# sch.net
KiCad netlist of a schematic drawn in Altium Designer
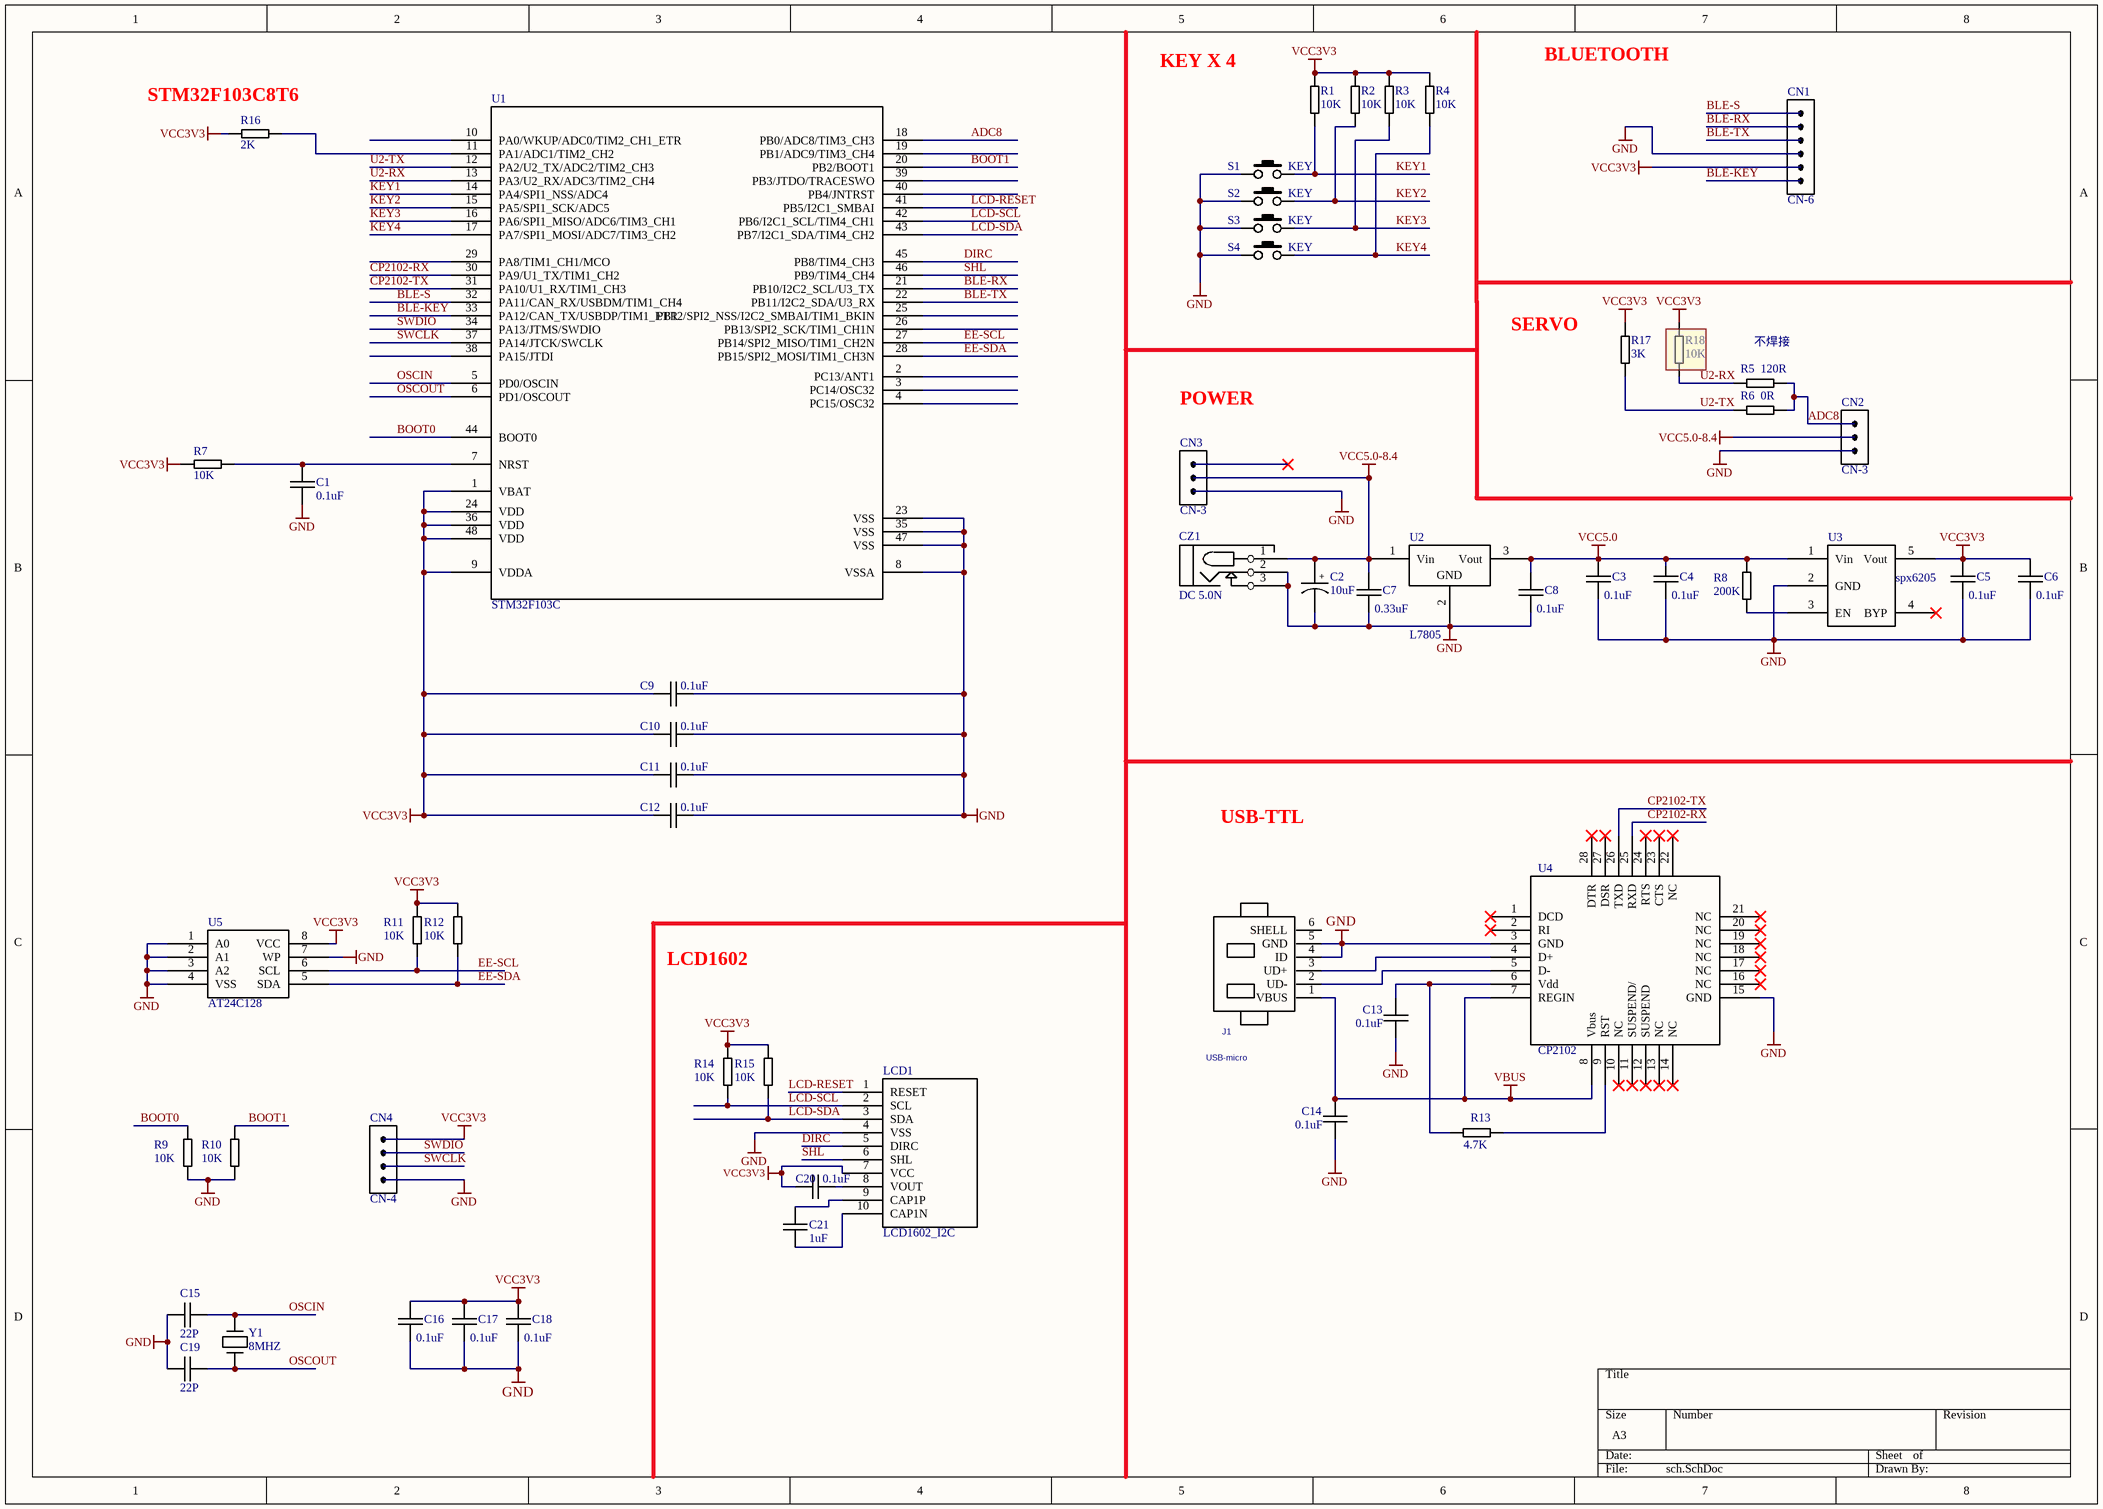
[diagram p0: sch.SchDoc]

(export (version "E")
  (design (tool "Eeschema 10.0.6"))
  (components
    (comp (ref "C1")
      (value "0.1uF")
      (footprint "CAP-0603")
      (description "Capacitor")
      (libsource (lib "综合元件") (part "CAP"))
    )
    (comp (ref "C2")
      (value "10uF")
      (footprint "CAP-A")
      (description "Polar Capacitor")
      (libsource (lib "1-Components") (part "CAP(POL)"))
    )
    (comp (ref "C3")
      (value "0.1uF")
      (footprint "CAP-0603")
      (description "Capacitor")
      (libsource (lib "综合元件") (part "CAP"))
    )
    (comp (ref "C4")
      (value "0.1uF")
      (footprint "CAP-0603")
      (description "Capacitor")
      (libsource (lib "综合元件") (part "CAP"))
    )
    (comp (ref "C5")
      (value "0.1uF")
      (footprint "CAP-0603")
      (description "Capacitor")
      (libsource (lib "综合元件") (part "CAP"))
    )
    (comp (ref "C6")
      (value "0.1uF")
      (footprint "CAP-0603")
      (description "Capacitor")
      (libsource (lib "综合元件") (part "CAP"))
    )
    (comp (ref "C7")
      (value "0.33uF")
      (footprint "CAP-0603")
      (description "Capacitor")
      (libsource (lib "综合元件") (part "CAP"))
    )
    (comp (ref "C8")
      (value "0.1uF")
      (footprint "CAP-0603")
      (description "Capacitor")
      (libsource (lib "综合元件") (part "CAP"))
    )
    (comp (ref "C9")
      (value "0.1uF")
      (footprint "CAP-0603")
      (description "Capacitor")
      (libsource (lib "综合元件") (part "CAP"))
    )
    (comp (ref "C10")
      (value "0.1uF")
      (footprint "CAP-0603")
      (description "Capacitor")
      (libsource (lib "综合元件") (part "CAP"))
    )
    (comp (ref "C11")
      (value "0.1uF")
      (footprint "CAP-0603")
      (description "Capacitor")
      (libsource (lib "综合元件") (part "CAP"))
    )
    (comp (ref "C12")
      (value "0.1uF")
      (footprint "CAP-0603")
      (description "Capacitor")
      (libsource (lib "综合元件") (part "CAP"))
    )
    (comp (ref "C13")
      (value "0.1uF")
      (footprint "CAP-0603")
      (description "Capacitor")
      (libsource (lib "综合元件") (part "CAP"))
    )
    (comp (ref "C14")
      (value "0.1uF")
      (footprint "CAP-0603")
      (description "Capacitor")
      (libsource (lib "综合元件") (part "CAP"))
    )
    (comp (ref "C15")
      (value "22P")
      (footprint "CAP-0603")
      (description "Capacitor")
      (libsource (lib "1-Components") (part "CAP"))
    )
    (comp (ref "C16")
      (value "0.1uF")
      (footprint "CAP-0603")
      (description "Capacitor")
      (libsource (lib "综合元件") (part "CAP"))
    )
    (comp (ref "C17")
      (value "0.1uF")
      (footprint "CAP-0603")
      (description "Capacitor")
      (libsource (lib "综合元件") (part "CAP"))
    )
    (comp (ref "C18")
      (value "0.1uF")
      (footprint "CAP-0603")
      (description "Capacitor")
      (libsource (lib "综合元件") (part "CAP"))
    )
    (comp (ref "C19")
      (value "22P")
      (footprint "CAP-0603")
      (description "Capacitor")
      (libsource (lib "1-Components") (part "CAP"))
    )
    (comp (ref "C20")
      (value "0.1uF")
      (footprint "CAP-0603")
      (description "Capacitor")
      (libsource (lib "综合元件") (part "CAP"))
    )
    (comp (ref "C21")
      (value "1uF")
      (footprint "CAP-0603")
      (description "Capacitor")
      (libsource (lib "综合元件") (part "CAP"))
    )
    (comp (ref "CN1") (value "CN-6") (footprint "CN-6") (libsource (lib "2-Connectors") (part "CN-6")))
    (comp (ref "CN2") (value "CN-3") (footprint "IDC-3×1") (libsource (lib "2-Connectors") (part "CN-3")))
    (comp (ref "CN3") (value "CN-3") (footprint "IDC-3×1") (libsource (lib "2-Connectors") (part "CN-3")))
    (comp (ref "CN4") (value "CN-4") (footprint "IDC-4×1") (libsource (lib "2-Connectors") (part "CN-4")))
    (comp (ref "CZ1")
      (value "DC 5.0N")
      (footprint "DC-005(N)")
      (libsource (lib "2-Connectors") (part "DC 5.0N"))
    )
    (comp (ref "J1")
      (value "USB-micro")
      (footprint "USB-MICRO")
      (libsource (lib "2-Connectors") (part "USB-micro"))
    )
    (comp (ref "LCD1")
      (value "LCD1602_I2C")
      (footprint "LCD-IIC")
      (description "LCD1602")
      (libsource (lib "6-Modulars") (part "LCD1602_I2C"))
    )
    (comp (ref "R1")
      (value "10K")
      (footprint "RES-0603")
      (description "Resistor")
      (libsource (lib "1-Components") (part "RES"))
    )
    (comp (ref "R2")
      (value "10K")
      (footprint "RES-0603")
      (description "Resistor")
      (libsource (lib "1-Components") (part "RES"))
    )
    (comp (ref "R3")
      (value "10K")
      (footprint "RES-0603")
      (description "Resistor")
      (libsource (lib "1-Components") (part "RES"))
    )
    (comp (ref "R4")
      (value "10K")
      (footprint "RES-0603")
      (description "Resistor")
      (libsource (lib "1-Components") (part "RES"))
    )
    (comp (ref "R5")
      (value "120R")
      (footprint "RES-0603")
      (description "Resistor")
      (libsource (lib "1-Components") (part "RES"))
    )
    (comp (ref "R6")
      (value "0R")
      (footprint "RES-0603")
      (description "Resistor")
      (libsource (lib "1-Components") (part "RES"))
    )
    (comp (ref "R7")
      (value "10K")
      (footprint "RES-0603")
      (description "Resistor")
      (libsource (lib "综合元件") (part "RES"))
    )
    (comp (ref "R8")
      (value "200K")
      (footprint "RES-0603")
      (description "Resistor")
      (libsource (lib "1-Components") (part "RES"))
    )
    (comp (ref "R9")
      (value "10K")
      (footprint "RES-0603")
      (description "Resistor")
      (libsource (lib "1-Components") (part "RES"))
    )
    (comp (ref "R10")
      (value "10K")
      (footprint "RES-0603")
      (description "Resistor")
      (libsource (lib "1-Components") (part "RES"))
    )
    (comp (ref "R11")
      (value "10K")
      (footprint "RES-0603")
      (description "Resistor")
      (libsource (lib "1-Components") (part "RES"))
    )
    (comp (ref "R12")
      (value "10K")
      (footprint "RES-0603")
      (description "Resistor")
      (libsource (lib "1-Components") (part "RES"))
    )
    (comp (ref "R13")
      (value "4.7K")
      (footprint "RES-0603")
      (description "Resistor")
      (libsource (lib "1-Components") (part "RES"))
    )
    (comp (ref "R14")
      (value "10K")
      (footprint "RES-0603")
      (description "Resistor")
      (libsource (lib "1-Components") (part "RES"))
    )
    (comp (ref "R15")
      (value "10K")
      (footprint "RES-0603")
      (description "Resistor")
      (libsource (lib "1-Components") (part "RES"))
    )
    (comp (ref "R16")
      (value "2K")
      (footprint "RES-0603")
      (description "Resistor")
      (libsource (lib "1-Components") (part "RES"))
    )
    (comp (ref "R17")
      (value "3K")
      (footprint "RES-0603")
      (description "Resistor")
      (libsource (lib "1-Components") (part "RES"))
    )
    (comp (ref "R18")
      (value "10K")
      (footprint "RES-0603")
      (description "Resistor")
      (libsource (lib "1-Components") (part "RES"))
    )
    (comp (ref "S1") (value "KEY") (footprint "KEY-4X4X1.5") (libsource (lib "2-Connectors") (part "KEY")))
    (comp (ref "S2") (value "KEY") (footprint "KEY-4X4X1.5") (libsource (lib "2-Connectors") (part "KEY")))
    (comp (ref "S3") (value "KEY") (footprint "KEY-4X4X1.5") (libsource (lib "2-Connectors") (part "KEY")))
    (comp (ref "S4") (value "KEY") (footprint "KEY-4X4X1.5") (libsource (lib "2-Connectors") (part "KEY")))
    (comp (ref "U1")
      (value "STM32F103C")
      (footprint "LQFP-48")
      (fields (field (name "PUBLISHER") "Altium Limited"))
      (libsource (lib "5-ICs Mcu") (part "STM32F103C(LQFP)"))
    )
    (comp (ref "U2") (value "L7805") (footprint "TO-252") (libsource (lib "3-ICs Normal") (part "78XX")))
    (comp (ref "U3")
      (value "spx6205")
      (footprint "SOT-23(5)")
      (libsource (lib "3-ICs Normal") (part "SP6205(FIXED)"))
    )
    (comp (ref "U4") (value "CP2102") (footprint "QFN-28") (libsource (lib "5-ICs Mcu") (part "MPU6050_1")))
    (comp (ref "U5")
      (value "AT24C128")
      (footprint "SOP-8(3.9)")
      (libsource (lib "3-ICs Normal") (part "AT24C128"))
    )
    (comp (ref "Y1")
      (value "8MHZ")
      (footprint "XTAL-2512")
      (description "Crystal")
      (libsource (lib "1-Components") (part "XTAL(1)"))
    )
  )
  (nets
    (net (code "1") (name "/ADC8") (class "Default")
      (node (ref "CN2") (pin "1") (pinfunction "1_1") (pintype "passive"))
      (node (ref "R5") (pin "2") (pinfunction "2_2") (pintype "passive"))
      (node (ref "R6") (pin "2") (pinfunction "2_2") (pintype "passive"))
      (node (ref "U1") (pin "18") (pinfunction "PB0/ADC8/TIM3_CH3_18") (pintype "passive"))
    )
    (net (code "2") (name "/BLE-KEY") (class "Default")
      (node (ref "CN1") (pin "6") (pinfunction "6_6") (pintype "passive"))
      (node (ref "U1") (pin "33") (pinfunction "PA12/CAN_TX/USBDP/TIM1_ETR_33") (pintype "passive"))
    )
    (net (code "3") (name "/BLE-RX") (class "Default")
      (node (ref "CN1") (pin "2") (pinfunction "2_2") (pintype "passive"))
      (node (ref "U1") (pin "21") (pinfunction "PB10/I2C2_SCL/U3_TX_21") (pintype "passive"))
    )
    (net (code "4") (name "/BLE-S") (class "Default")
      (node (ref "CN1") (pin "1") (pinfunction "1_1") (pintype "passive"))
      (node (ref "U1") (pin "32") (pinfunction "PA11/CAN_RX/USBDM/TIM1_CH4_32") (pintype "passive"))
    )
    (net (code "5") (name "/BLE-TX") (class "Default")
      (node (ref "CN1") (pin "3") (pinfunction "3_3") (pintype "passive"))
      (node (ref "U1") (pin "22") (pinfunction "PB11/I2C2_SDA/U3_RX_22") (pintype "passive"))
    )
    (net (code "6") (name "/BOOT0") (class "Default")
      (node (ref "R9") (pin "1") (pinfunction "1_1") (pintype "passive"))
      (node (ref "U1") (pin "44") (pinfunction "BOOT0_44") (pintype "passive"))
    )
    (net (code "7") (name "/BOOT1") (class "Default")
      (node (ref "R10") (pin "1") (pinfunction "1_1") (pintype "passive"))
      (node (ref "U1") (pin "20") (pinfunction "PB2/BOOT1_20") (pintype "passive"))
    )
    (net (code "8") (name "/CP2102-RX") (class "Default")
      (node (ref "U1") (pin "30") (pinfunction "PA9/U1_TX/TIM1_CH2_30") (pintype "passive"))
      (node (ref "U4") (pin "25") (pinfunction "RXD_25") (pintype "passive"))
    )
    (net (code "9") (name "/CP2102-TX") (class "Default")
      (node (ref "U1") (pin "31") (pinfunction "PA10/U1_RX/TIM1_CH3_31") (pintype "passive"))
      (node (ref "U4") (pin "26") (pinfunction "TXD_26") (pintype "passive"))
    )
    (net (code "10") (name "/DIRC") (class "Default")
      (node (ref "LCD1") (pin "5") (pinfunction "DIRC_5") (pintype "passive"))
      (node (ref "U1") (pin "45") (pinfunction "PB8/TIM4_CH3_45") (pintype "passive"))
    )
    (net (code "11") (name "/EE-SCL") (class "Default")
      (node (ref "R11") (pin "2") (pinfunction "2_2") (pintype "passive"))
      (node (ref "U1") (pin "27") (pinfunction "PB14/SPI2_MISO/TIM1_CH2N_27") (pintype "passive"))
      (node (ref "U5") (pin "6") (pinfunction "SCL_6") (pintype "passive"))
    )
    (net (code "12") (name "/EE-SDA") (class "Default")
      (node (ref "R12") (pin "2") (pinfunction "2_2") (pintype "passive"))
      (node (ref "U1") (pin "28") (pinfunction "PB15/SPI2_MOSI/TIM1_CH3N_28") (pintype "passive"))
      (node (ref "U5") (pin "5") (pinfunction "SDA_5") (pintype "passive"))
    )
    (net (code "13") (name "/KEY1") (class "Default")
      (node (ref "R1") (pin "1") (pinfunction "1_1") (pintype "passive"))
      (node (ref "S1") (pin "2") (pinfunction "2_2") (pintype "passive"))
      (node (ref "U1") (pin "14") (pinfunction "PA4/SPI1_NSS/ADC4_14") (pintype "passive"))
    )
    (net (code "14") (name "/KEY2") (class "Default")
      (node (ref "R2") (pin "1") (pinfunction "1_1") (pintype "passive"))
      (node (ref "S2") (pin "2") (pinfunction "2_2") (pintype "passive"))
      (node (ref "U1") (pin "15") (pinfunction "PA5/SPI1_SCK/ADC5_15") (pintype "passive"))
    )
    (net (code "15") (name "/KEY3") (class "Default")
      (node (ref "R3") (pin "1") (pinfunction "1_1") (pintype "passive"))
      (node (ref "S3") (pin "2") (pinfunction "2_2") (pintype "passive"))
      (node (ref "U1") (pin "16") (pinfunction "PA6/SPI1_MISO/ADC6/TIM3_CH1_16") (pintype "passive"))
    )
    (net (code "16") (name "/KEY4") (class "Default")
      (node (ref "R4") (pin "1") (pinfunction "1_1") (pintype "passive"))
      (node (ref "S4") (pin "2") (pinfunction "2_2") (pintype "passive"))
      (node (ref "U1") (pin "17") (pinfunction "PA7/SPI1_MOSI/ADC7/TIM3_CH2_17") (pintype "passive"))
    )
    (net (code "17") (name "/LCD-RESET") (class "Default")
      (node (ref "LCD1") (pin "1") (pinfunction "RESET_1") (pintype "passive"))
      (node (ref "U1") (pin "41") (pinfunction "PB5/I2C1_SMBAI_41") (pintype "passive"))
    )
    (net (code "18") (name "/LCD-SCL") (class "Default")
      (node (ref "LCD1") (pin "2") (pinfunction "SCL_2") (pintype "passive"))
      (node (ref "R14") (pin "2") (pinfunction "2_2") (pintype "passive"))
      (node (ref "U1") (pin "42") (pinfunction "PB6/I2C1_SCL/TIM4_CH1_42") (pintype "passive"))
    )
    (net (code "19") (name "/LCD-SDA") (class "Default")
      (node (ref "LCD1") (pin "3") (pinfunction "SDA_3") (pintype "passive"))
      (node (ref "R15") (pin "2") (pinfunction "2_2") (pintype "passive"))
      (node (ref "U1") (pin "43") (pinfunction "PB7/I2C1_SDA/TIM4_CH2_43") (pintype "passive"))
    )
    (net (code "20") (name "/OSCIN") (class "Default")
      (node (ref "C15") (pin "2") (pinfunction "2_2") (pintype "passive"))
      (node (ref "U1") (pin "5") (pinfunction "PD0/OSCIN_5") (pintype "passive"))
      (node (ref "Y1") (pin "2") (pinfunction "2_2") (pintype "passive"))
    )
    (net (code "21") (name "/OSCOUT") (class "Default")
      (node (ref "C19") (pin "2") (pinfunction "2_2") (pintype "passive"))
      (node (ref "U1") (pin "6") (pinfunction "PD1/OSCOUT_6") (pintype "passive"))
      (node (ref "Y1") (pin "1") (pinfunction "1_1") (pintype "passive"))
    )
    (net (code "22") (name "/SHL") (class "Default")
      (node (ref "LCD1") (pin "6") (pinfunction "SHL_6") (pintype "passive"))
      (node (ref "U1") (pin "46") (pinfunction "PB9/TIM4_CH4_46") (pintype "passive"))
    )
    (net (code "23") (name "/SWCLK") (class "Default")
      (node (ref "CN4") (pin "3") (pinfunction "3_3") (pintype "passive"))
      (node (ref "U1") (pin "37") (pinfunction "PA14/JTCK/SWCLK_37") (pintype "passive"))
    )
    (net (code "24") (name "/SWDIO") (class "Default")
      (node (ref "CN4") (pin "2") (pinfunction "2_2") (pintype "passive"))
      (node (ref "U1") (pin "34") (pinfunction "PA13/JTMS/SWDIO_34") (pintype "passive"))
    )
    (net (code "25") (name "/U2-RX") (class "Default")
      (node (ref "R18") (pin "1") (pinfunction "1_1") (pintype "passive"))
      (node (ref "R5") (pin "1") (pinfunction "1_1") (pintype "passive"))
      (node (ref "U1") (pin "13") (pinfunction "PA3/U2_RX/ADC3/TIM2_CH4_13") (pintype "passive"))
    )
    (net (code "26") (name "/U2-TX") (class "Default")
      (node (ref "R17") (pin "1") (pinfunction "1_1") (pintype "passive"))
      (node (ref "R6") (pin "1") (pinfunction "1_1") (pintype "passive"))
      (node (ref "U1") (pin "12") (pinfunction "PA2/U2_TX/ADC2/TIM2_CH3_12") (pintype "passive"))
    )
    (net (code "27") (name "GND") (class "Default")
      (node (ref "C1") (pin "2") (pinfunction "2_2") (pintype "passive"))
      (node (ref "C10") (pin "1") (pinfunction "1_1") (pintype "passive"))
      (node (ref "C11") (pin "1") (pinfunction "1_1") (pintype "passive"))
      (node (ref "C12") (pin "1") (pinfunction "1_1") (pintype "passive"))
      (node (ref "C13") (pin "2") (pinfunction "2_2") (pintype "passive"))
      (node (ref "C14") (pin "2") (pinfunction "2_2") (pintype "passive"))
      (node (ref "C15") (pin "1") (pinfunction "1_1") (pintype "passive"))
      (node (ref "C16") (pin "2") (pinfunction "2_2") (pintype "passive"))
      (node (ref "C17") (pin "2") (pinfunction "2_2") (pintype "passive"))
      (node (ref "C18") (pin "2") (pinfunction "2_2") (pintype "passive"))
      (node (ref "C19") (pin "1") (pinfunction "1_1") (pintype "passive"))
      (node (ref "C2") (pin "2") (pinfunction "2_2") (pintype "passive"))
      (node (ref "C3") (pin "2") (pinfunction "2_2") (pintype "passive"))
      (node (ref "C4") (pin "2") (pinfunction "2_2") (pintype "passive"))
      (node (ref "C5") (pin "2") (pinfunction "2_2") (pintype "passive"))
      (node (ref "C6") (pin "2") (pinfunction "2_2") (pintype "passive"))
      (node (ref "C7") (pin "2") (pinfunction "2_2") (pintype "passive"))
      (node (ref "C8") (pin "2") (pinfunction "2_2") (pintype "passive"))
      (node (ref "C9") (pin "1") (pinfunction "1_1") (pintype "passive"))
      (node (ref "CN1") (pin "4") (pinfunction "4_4") (pintype "passive"))
      (node (ref "CN2") (pin "3") (pinfunction "3_3") (pintype "passive"))
      (node (ref "CN3") (pin "3") (pinfunction "3_3") (pintype "passive"))
      (node (ref "CN4") (pin "4") (pinfunction "4_4") (pintype "passive"))
      (node (ref "CZ1") (pin "2") (pinfunction "A_2") (pintype "passive"))
      (node (ref "CZ1") (pin "3") (pinfunction "B_3") (pintype "passive"))
      (node (ref "J1") (pin "4") (pinfunction "ID_4") (pintype "passive"))
      (node (ref "J1") (pin "5") (pinfunction "GND_5") (pintype "passive"))
      (node (ref "LCD1") (pin "4") (pinfunction "VSS_4") (pintype "passive"))
      (node (ref "R10") (pin "2") (pinfunction "2_2") (pintype "passive"))
      (node (ref "R9") (pin "2") (pinfunction "2_2") (pintype "passive"))
      (node (ref "S1") (pin "1") (pinfunction "1_1") (pintype "passive"))
      (node (ref "S2") (pin "1") (pinfunction "1_1") (pintype "passive"))
      (node (ref "S3") (pin "1") (pinfunction "1_1") (pintype "passive"))
      (node (ref "S4") (pin "1") (pinfunction "1_1") (pintype "passive"))
      (node (ref "U1") (pin "23") (pinfunction "VSS_23") (pintype "passive"))
      (node (ref "U1") (pin "35") (pinfunction "VSS_35") (pintype "passive"))
      (node (ref "U1") (pin "47") (pinfunction "VSS_47") (pintype "passive"))
      (node (ref "U1") (pin "8") (pinfunction "VSSA_8") (pintype "passive"))
      (node (ref "U2") (pin "2") (pinfunction "GND_2") (pintype "passive"))
      (node (ref "U3") (pin "2") (pinfunction "GND_2") (pintype "passive"))
      (node (ref "U4") (pin "15") (pinfunction "GND_15") (pintype "passive"))
      (node (ref "U4") (pin "3") (pinfunction "GND_3") (pintype "passive"))
      (node (ref "U5") (pin "1") (pinfunction "A0_1") (pintype "passive"))
      (node (ref "U5") (pin "2") (pinfunction "A1_2") (pintype "passive"))
      (node (ref "U5") (pin "3") (pinfunction "A2_3") (pintype "passive"))
      (node (ref "U5") (pin "4") (pinfunction "VSS_4") (pintype "passive"))
      (node (ref "U5") (pin "7") (pinfunction "WP_7") (pintype "passive"))
    )
    (net (code "28") (name "Net-(J1-UD+)") (class "Default")
      (node (ref "J1") (pin "3") (pinfunction "UD+_3") (pintype "passive"))
      (node (ref "U4") (pin "4") (pinfunction "D+_4") (pintype "passive"))
    )
    (net (code "29") (name "Net-(J1-UD-)") (class "Default")
      (node (ref "J1") (pin "2") (pinfunction "UD-_2") (pintype "passive"))
      (node (ref "U4") (pin "5") (pinfunction "D-_5") (pintype "passive"))
    )
    (net (code "30") (name "Net-(LCD1-CAP1N)") (class "Default")
      (node (ref "C21") (pin "2") (pinfunction "2_2") (pintype "passive"))
      (node (ref "LCD1") (pin "10") (pinfunction "CAP1N_10") (pintype "passive"))
    )
    (net (code "31") (name "Net-(LCD1-CAP1P)") (class "Default")
      (node (ref "C21") (pin "1") (pinfunction "1_1") (pintype "passive"))
      (node (ref "LCD1") (pin "9") (pinfunction "CAP1P_9") (pintype "passive"))
    )
    (net (code "32") (name "Net-(LCD1-VOUT)") (class "Default")
      (node (ref "C20") (pin "2") (pinfunction "2_2") (pintype "passive"))
      (node (ref "LCD1") (pin "8") (pinfunction "VOUT_8") (pintype "passive"))
    )
    (net (code "33") (name "Net-(U1-NRST)") (class "Default")
      (node (ref "C1") (pin "1") (pinfunction "1_1") (pintype "passive"))
      (node (ref "R7") (pin "2") (pinfunction "2_2") (pintype "passive"))
      (node (ref "U1") (pin "7") (pinfunction "NRST_7") (pintype "passive"))
    )
    (net (code "34") (name "Net-(U1-PA1{slash}ADC1{slash}TIM2_CH2)") (class "Default")
      (node (ref "R16") (pin "1") (pinfunction "1_1") (pintype "passive"))
      (node (ref "U1") (pin "11") (pinfunction "PA1/ADC1/TIM2_CH2_11") (pintype "passive"))
    )
    (net (code "35") (name "Net-(U3-EN)") (class "Default")
      (node (ref "R8") (pin "2") (pinfunction "2_2") (pintype "passive"))
      (node (ref "U3") (pin "3") (pinfunction "EN_3") (pintype "passive"))
    )
    (net (code "36") (name "Net-(U4-RST)") (class "Default")
      (node (ref "R13") (pin "2") (pinfunction "2_2") (pintype "passive"))
      (node (ref "U4") (pin "9") (pinfunction "RST_9") (pintype "passive"))
    )
    (net (code "37") (name "Net-(U4-Vdd)") (class "Default")
      (node (ref "C13") (pin "1") (pinfunction "1_1") (pintype "passive"))
      (node (ref "R13") (pin "1") (pinfunction "1_1") (pintype "passive"))
      (node (ref "U4") (pin "6") (pinfunction "Vdd_6") (pintype "passive"))
    )
    (net (code "38") (name "VBUS") (class "Default")
      (node (ref "C14") (pin "1") (pinfunction "1_1") (pintype "passive"))
      (node (ref "J1") (pin "1") (pinfunction "VBUS_1") (pintype "passive"))
      (node (ref "U4") (pin "7") (pinfunction "REGIN_7") (pintype "passive"))
      (node (ref "U4") (pin "8") (pinfunction "Vbus_8") (pintype "passive"))
    )
    (net (code "39") (name "VCC3V3") (class "Default")
      (node (ref "C10") (pin "2") (pinfunction "2_2") (pintype "passive"))
      (node (ref "C11") (pin "2") (pinfunction "2_2") (pintype "passive"))
      (node (ref "C12") (pin "2") (pinfunction "2_2") (pintype "passive"))
      (node (ref "C16") (pin "1") (pinfunction "1_1") (pintype "passive"))
      (node (ref "C17") (pin "1") (pinfunction "1_1") (pintype "passive"))
      (node (ref "C18") (pin "1") (pinfunction "1_1") (pintype "passive"))
      (node (ref "C20") (pin "1") (pinfunction "1_1") (pintype "passive"))
      (node (ref "C5") (pin "1") (pinfunction "1_1") (pintype "passive"))
      (node (ref "C6") (pin "1") (pinfunction "1_1") (pintype "passive"))
      (node (ref "C9") (pin "2") (pinfunction "2_2") (pintype "passive"))
      (node (ref "CN1") (pin "5") (pinfunction "5_5") (pintype "passive"))
      (node (ref "CN4") (pin "1") (pinfunction "1_1") (pintype "passive"))
      (node (ref "LCD1") (pin "7") (pinfunction "VCC_7") (pintype "passive"))
      (node (ref "R1") (pin "2") (pinfunction "2_2") (pintype "passive"))
      (node (ref "R11") (pin "1") (pinfunction "1_1") (pintype "passive"))
      (node (ref "R12") (pin "1") (pinfunction "1_1") (pintype "passive"))
      (node (ref "R14") (pin "1") (pinfunction "1_1") (pintype "passive"))
      (node (ref "R15") (pin "1") (pinfunction "1_1") (pintype "passive"))
      (node (ref "R16") (pin "2") (pinfunction "2_2") (pintype "passive"))
      (node (ref "R17") (pin "2") (pinfunction "2_2") (pintype "passive"))
      (node (ref "R18") (pin "2") (pinfunction "2_2") (pintype "passive"))
      (node (ref "R2") (pin "2") (pinfunction "2_2") (pintype "passive"))
      (node (ref "R3") (pin "2") (pinfunction "2_2") (pintype "passive"))
      (node (ref "R4") (pin "2") (pinfunction "2_2") (pintype "passive"))
      (node (ref "R7") (pin "1") (pinfunction "1_1") (pintype "passive"))
      (node (ref "U1") (pin "1") (pinfunction "VBAT_1") (pintype "passive"))
      (node (ref "U1") (pin "24") (pinfunction "VDD_24") (pintype "passive"))
      (node (ref "U1") (pin "36") (pinfunction "VDD_36") (pintype "passive"))
      (node (ref "U1") (pin "48") (pinfunction "VDD_48") (pintype "passive"))
      (node (ref "U1") (pin "9") (pinfunction "VDDA_9") (pintype "passive"))
      (node (ref "U3") (pin "5") (pinfunction "Vout_5") (pintype "passive"))
      (node (ref "U5") (pin "8") (pinfunction "VCC_8") (pintype "passive"))
    )
    (net (code "40") (name "VCC5.0") (class "Default")
      (node (ref "C3") (pin "1") (pinfunction "1_1") (pintype "passive"))
      (node (ref "C4") (pin "1") (pinfunction "1_1") (pintype "passive"))
      (node (ref "C8") (pin "1") (pinfunction "1_1") (pintype "passive"))
      (node (ref "R8") (pin "1") (pinfunction "1_1") (pintype "passive"))
      (node (ref "U2") (pin "3") (pinfunction "Vout_3") (pintype "passive"))
      (node (ref "U3") (pin "1") (pinfunction "Vin_1") (pintype "passive"))
    )
    (net (code "41") (name "VCC5.0-8.4") (class "Default")
      (node (ref "C2") (pin "1") (pinfunction "1_1") (pintype "passive"))
      (node (ref "C7") (pin "1") (pinfunction "1_1") (pintype "passive"))
      (node (ref "CN2") (pin "2") (pinfunction "2_2") (pintype "passive"))
      (node (ref "CN3") (pin "2") (pinfunction "2_2") (pintype "passive"))
      (node (ref "CZ1") (pin "1") (pinfunction "+_1") (pintype "passive"))
      (node (ref "U2") (pin "1") (pinfunction "Vin_1") (pintype "passive"))
    )
    (net (code "42") (name "unconnected-(CN3-Pad1)") (class "Default")
      (node (ref "CN3") (pin "1") (pinfunction "1_1") (pintype "passive+no_connect"))
    )
    (net (code "43") (name "unconnected-(J1-SHELL-Pad6)") (class "Default")
      (node (ref "J1") (pin "6") (pinfunction "SHELL_6") (pintype "passive"))
    )
    (net (code "44") (name "unconnected-(U1-PA0{slash}WKUP{slash}ADC0{slash}TIM2_CH1_ETR-Pad10)") (class "Default")
      (node (ref "U1") (pin "10") (pinfunction "PA0/WKUP/ADC0/TIM2_CH1_ETR_10") (pintype "passive"))
    )
    (net (code "45") (name "unconnected-(U1-PA8{slash}TIM1_CH1{slash}MCO-Pad29)") (class "Default")
      (node (ref "U1") (pin "29") (pinfunction "PA8/TIM1_CH1/MCO_29") (pintype "passive"))
    )
    (net (code "46") (name "unconnected-(U1-PA15{slash}JTDI-Pad38)") (class "Default")
      (node (ref "U1") (pin "38") (pinfunction "PA15/JTDI_38") (pintype "passive"))
    )
    (net (code "47") (name "unconnected-(U1-PB1{slash}ADC9{slash}TIM3_CH4-Pad19)") (class "Default")
      (node (ref "U1") (pin "19") (pinfunction "PB1/ADC9/TIM3_CH4_19") (pintype "passive"))
    )
    (net (code "48") (name "unconnected-(U1-PB3{slash}JTDO{slash}TRACESWO-Pad39)") (class "Default")
      (node (ref "U1") (pin "39") (pinfunction "PB3/JTDO/TRACESWO_39") (pintype "passive"))
    )
    (net (code "49") (name "unconnected-(U1-PB4{slash}JNTRST-Pad40)") (class "Default")
      (node (ref "U1") (pin "40") (pinfunction "PB4/JNTRST_40") (pintype "passive"))
    )
    (net (code "50") (name "unconnected-(U1-PB12{slash}SPI2_NSS{slash}I2C2_SMBAI{slash}TIM1_BKIN-Pad25)") (class "Default")
      (node (ref "U1") (pin "25") (pinfunction "PB12/SPI2_NSS/I2C2_SMBAI/TIM1_BKIN_25") (pintype "passive"))
    )
    (net (code "51") (name "unconnected-(U1-PB13{slash}SPI2_SCK{slash}TIM1_CH1N-Pad26)") (class "Default")
      (node (ref "U1") (pin "26") (pinfunction "PB13/SPI2_SCK/TIM1_CH1N_26") (pintype "passive"))
    )
    (net (code "52") (name "unconnected-(U1-PC13{slash}ANT1-Pad2)") (class "Default")
      (node (ref "U1") (pin "2") (pinfunction "PC13/ANT1_2") (pintype "passive"))
    )
    (net (code "53") (name "unconnected-(U1-PC14{slash}OSC32-Pad3)") (class "Default")
      (node (ref "U1") (pin "3") (pinfunction "PC14/OSC32_3") (pintype "passive"))
    )
    (net (code "54") (name "unconnected-(U1-PC15{slash}OSC32-Pad4)") (class "Default")
      (node (ref "U1") (pin "4") (pinfunction "PC15/OSC32_4") (pintype "passive"))
    )
    (net (code "55") (name "unconnected-(U3-BYP-Pad4)") (class "Default")
      (node (ref "U3") (pin "4") (pinfunction "BYP_4") (pintype "passive+no_connect"))
    )
    (net (code "56") (name "unconnected-(U4-CTS-Pad23)") (class "Default")
      (node (ref "U4") (pin "23") (pinfunction "CTS_23") (pintype "passive+no_connect"))
    )
    (net (code "57") (name "unconnected-(U4-DCD-Pad1)") (class "Default")
      (node (ref "U4") (pin "1") (pinfunction "DCD_1") (pintype "passive+no_connect"))
    )
    (net (code "58") (name "unconnected-(U4-DSR-Pad27)") (class "Default")
      (node (ref "U4") (pin "27") (pinfunction "DSR_27") (pintype "passive+no_connect"))
    )
    (net (code "59") (name "unconnected-(U4-DTR-Pad28)") (class "Default")
      (node (ref "U4") (pin "28") (pinfunction "DTR_28") (pintype "passive+no_connect"))
    )
    (net (code "60") (name "unconnected-(U4-NC-Pad10)") (class "Default")
      (node (ref "U4") (pin "10") (pinfunction "NC_10") (pintype "passive+no_connect"))
    )
    (net (code "61") (name "unconnected-(U4-NC-Pad13)") (class "Default")
      (node (ref "U4") (pin "13") (pinfunction "NC_13") (pintype "passive+no_connect"))
    )
    (net (code "62") (name "unconnected-(U4-NC-Pad14)") (class "Default")
      (node (ref "U4") (pin "14") (pinfunction "NC_14") (pintype "passive+no_connect"))
    )
    (net (code "63") (name "unconnected-(U4-NC-Pad16)") (class "Default")
      (node (ref "U4") (pin "16") (pinfunction "NC_16") (pintype "passive+no_connect"))
    )
    (net (code "64") (name "unconnected-(U4-NC-Pad17)") (class "Default")
      (node (ref "U4") (pin "17") (pinfunction "NC_17") (pintype "passive+no_connect"))
    )
    (net (code "65") (name "unconnected-(U4-NC-Pad18)") (class "Default")
      (node (ref "U4") (pin "18") (pinfunction "NC_18") (pintype "passive+no_connect"))
    )
    (net (code "66") (name "unconnected-(U4-NC-Pad19)") (class "Default")
      (node (ref "U4") (pin "19") (pinfunction "NC_19") (pintype "passive+no_connect"))
    )
    (net (code "67") (name "unconnected-(U4-NC-Pad20)") (class "Default")
      (node (ref "U4") (pin "20") (pinfunction "NC_20") (pintype "passive+no_connect"))
    )
    (net (code "68") (name "unconnected-(U4-NC-Pad21)") (class "Default")
      (node (ref "U4") (pin "21") (pinfunction "NC_21") (pintype "passive+no_connect"))
    )
    (net (code "69") (name "unconnected-(U4-NC-Pad22)") (class "Default")
      (node (ref "U4") (pin "22") (pinfunction "NC_22") (pintype "passive+no_connect"))
    )
    (net (code "70") (name "unconnected-(U4-RI-Pad2)") (class "Default")
      (node (ref "U4") (pin "2") (pinfunction "RI_2") (pintype "passive+no_connect"))
    )
    (net (code "71") (name "unconnected-(U4-RTS-Pad24)") (class "Default")
      (node (ref "U4") (pin "24") (pinfunction "RTS_24") (pintype "passive+no_connect"))
    )
    (net (code "72") (name "unconnected-(U4-SUSPEND-Pad12)") (class "Default")
      (node (ref "U4") (pin "12") (pinfunction "SUSPEND_12") (pintype "passive+no_connect"))
    )
    (net (code "73") (name "unconnected-(U4-SUSPEND{slash}-Pad11)") (class "Default")
      (node (ref "U4") (pin "11") (pinfunction "SUSPEND/_11") (pintype "passive+no_connect"))
    )
  )
)
